# 1.net
KiCad netlist of a schematic drawn in Altium Designer
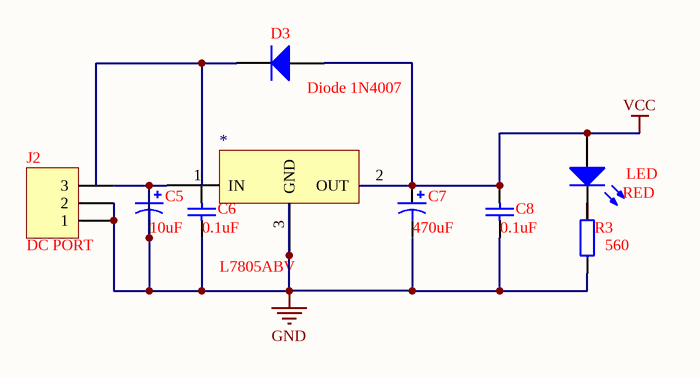
[diagram p0: 1.SchDoc]

(export (version "E")
  (design (tool "Eeschema 10.0.6"))
  (components
    (comp (ref "*") (value "L7805ABV") (libsource (lib "Schlib1") (part "L7805ABV")))
    (comp (ref "C5")
      (value "10uF")
      (footprint "RB7.6-15")
      (description "Polarized Capacitor (Radial)")
      (fields (field (name "Comment") "Cap Pol1") (field (name "PUBLISHER") "Altium Limited"))
      (libsource (lib "Miscellaneous Devices") (part "Cap Pol1"))
    )
    (comp (ref "C6")
      (value "0.1uF")
      (footprint "0402")
      (description "Capacitor (Semiconductor SIM Model)")
      (fields (field (name "Comment") "Cap Semi") (field (name "PUBLISHER") "Altium Limited"))
      (libsource (lib "Miscellaneous Devices") (part "Cap Semi"))
    )
    (comp (ref "C7")
      (value "470uF")
      (footprint "1812")
      (description "Polarized Capacitor (Surface Mount)")
      (fields (field (name "Comment") "Cap Pol3") (field (name "PUBLISHER") "Altium Limited"))
      (libsource (lib "Miscellaneous Devices") (part "Cap Pol3"))
    )
    (comp (ref "C8")
      (value "0.1uF")
      (footprint "0402")
      (description "Capacitor (Semiconductor SIM Model)")
      (fields (field (name "Comment") "Cap Semi") (field (name "PUBLISHER") "Altium Limited"))
      (libsource (lib "Miscellaneous Devices") (part "Cap Semi"))
    )
    (comp (ref "D3")
      (value "Diode 1N4007")
      (footprint "SMC")
      (description "Default Diode")
      (fields (field (name "PUBLISHER") "Altium Limited"))
      (libsource (lib "Miscellaneous Devices") (part "Diode"))
    )
    (comp (ref "J2")
      (value "DC PORT")
      (footprint "HDR1X3")
      (description "Header, 3-Pin")
      (fields (field (name "PUBLISHER") "Altium Limited"))
      (libsource (lib "Miscellaneous Connectors") (part "Header 3"))
    )
    (comp (ref "LED")
      (value "RED")
      (footprint "LED-0")
      (description "Typical INFRARED GaAs LED")
      (fields (field (name "PUBLISHER") "Altium Limited"))
      (libsource (lib "Miscellaneous Devices") (part "LED0"))
    )
    (comp (ref "R3")
      (value "560")
      (footprint "AXIAL-0.4")
      (description "Resistor")
      (fields (field (name "Comment") "Res2") (field (name "PUBLISHER") "Altium Limited"))
      (libsource (lib "Miscellaneous Devices") (part "Res2"))
    )
  )
  (nets
    (net (code "1") (name "GND") (class "Default")
      (node (ref "*") (pin "1") (pinfunction "IN_1") (pintype "passive"))
      (node (ref "*") (pin "3") (pinfunction "GND_3") (pintype "passive"))
      (node (ref "C5") (pin "1") (pinfunction "1_1") (pintype "passive"))
      (node (ref "C5") (pin "2") (pinfunction "2_2") (pintype "passive"))
      (node (ref "C6") (pin "1") (pinfunction "1_1") (pintype "passive"))
      (node (ref "C7") (pin "2") (pinfunction "2_2") (pintype "passive"))
      (node (ref "C8") (pin "1") (pinfunction "1_1") (pintype "passive"))
      (node (ref "J2") (pin "1") (pinfunction "1_1") (pintype "passive"))
      (node (ref "J2") (pin "2") (pinfunction "2_2") (pintype "passive"))
      (node (ref "J2") (pin "3") (pinfunction "3_3") (pintype "passive"))
      (node (ref "R3") (pin "2") (pinfunction "2_2") (pintype "passive"))
    )
    (net (code "2") (name "Net-(D3-K)") (class "Default")
      (node (ref "C6") (pin "2") (pinfunction "2_2") (pintype "passive"))
      (node (ref "D3") (pin "2") (pinfunction "K_2") (pintype "passive"))
    )
    (net (code "3") (name "VCC") (class "Default")
      (node (ref "*") (pin "2") (pinfunction "OUT_2") (pintype "passive"))
      (node (ref "C7") (pin "1") (pinfunction "1_1") (pintype "passive"))
      (node (ref "C8") (pin "2") (pinfunction "2_2") (pintype "passive"))
      (node (ref "D3") (pin "1") (pinfunction "A_1") (pintype "passive"))
      (node (ref "LED") (pin "1") (pinfunction "A_1") (pintype "passive"))
    )
    (net (code "4") (name "unconnected-(LED-K-Pad2)") (class "Default")
      (node (ref "LED") (pin "2") (pinfunction "K_2") (pintype "passive"))
    )
    (net (code "5") (name "unconnected-(R3-Pad1)") (class "Default")
      (node (ref "R3") (pin "1") (pinfunction "1_1") (pintype "passive"))
    )
  )
)
